# ESP8266.net
KiCad netlist of a schematic drawn in Altium Designer
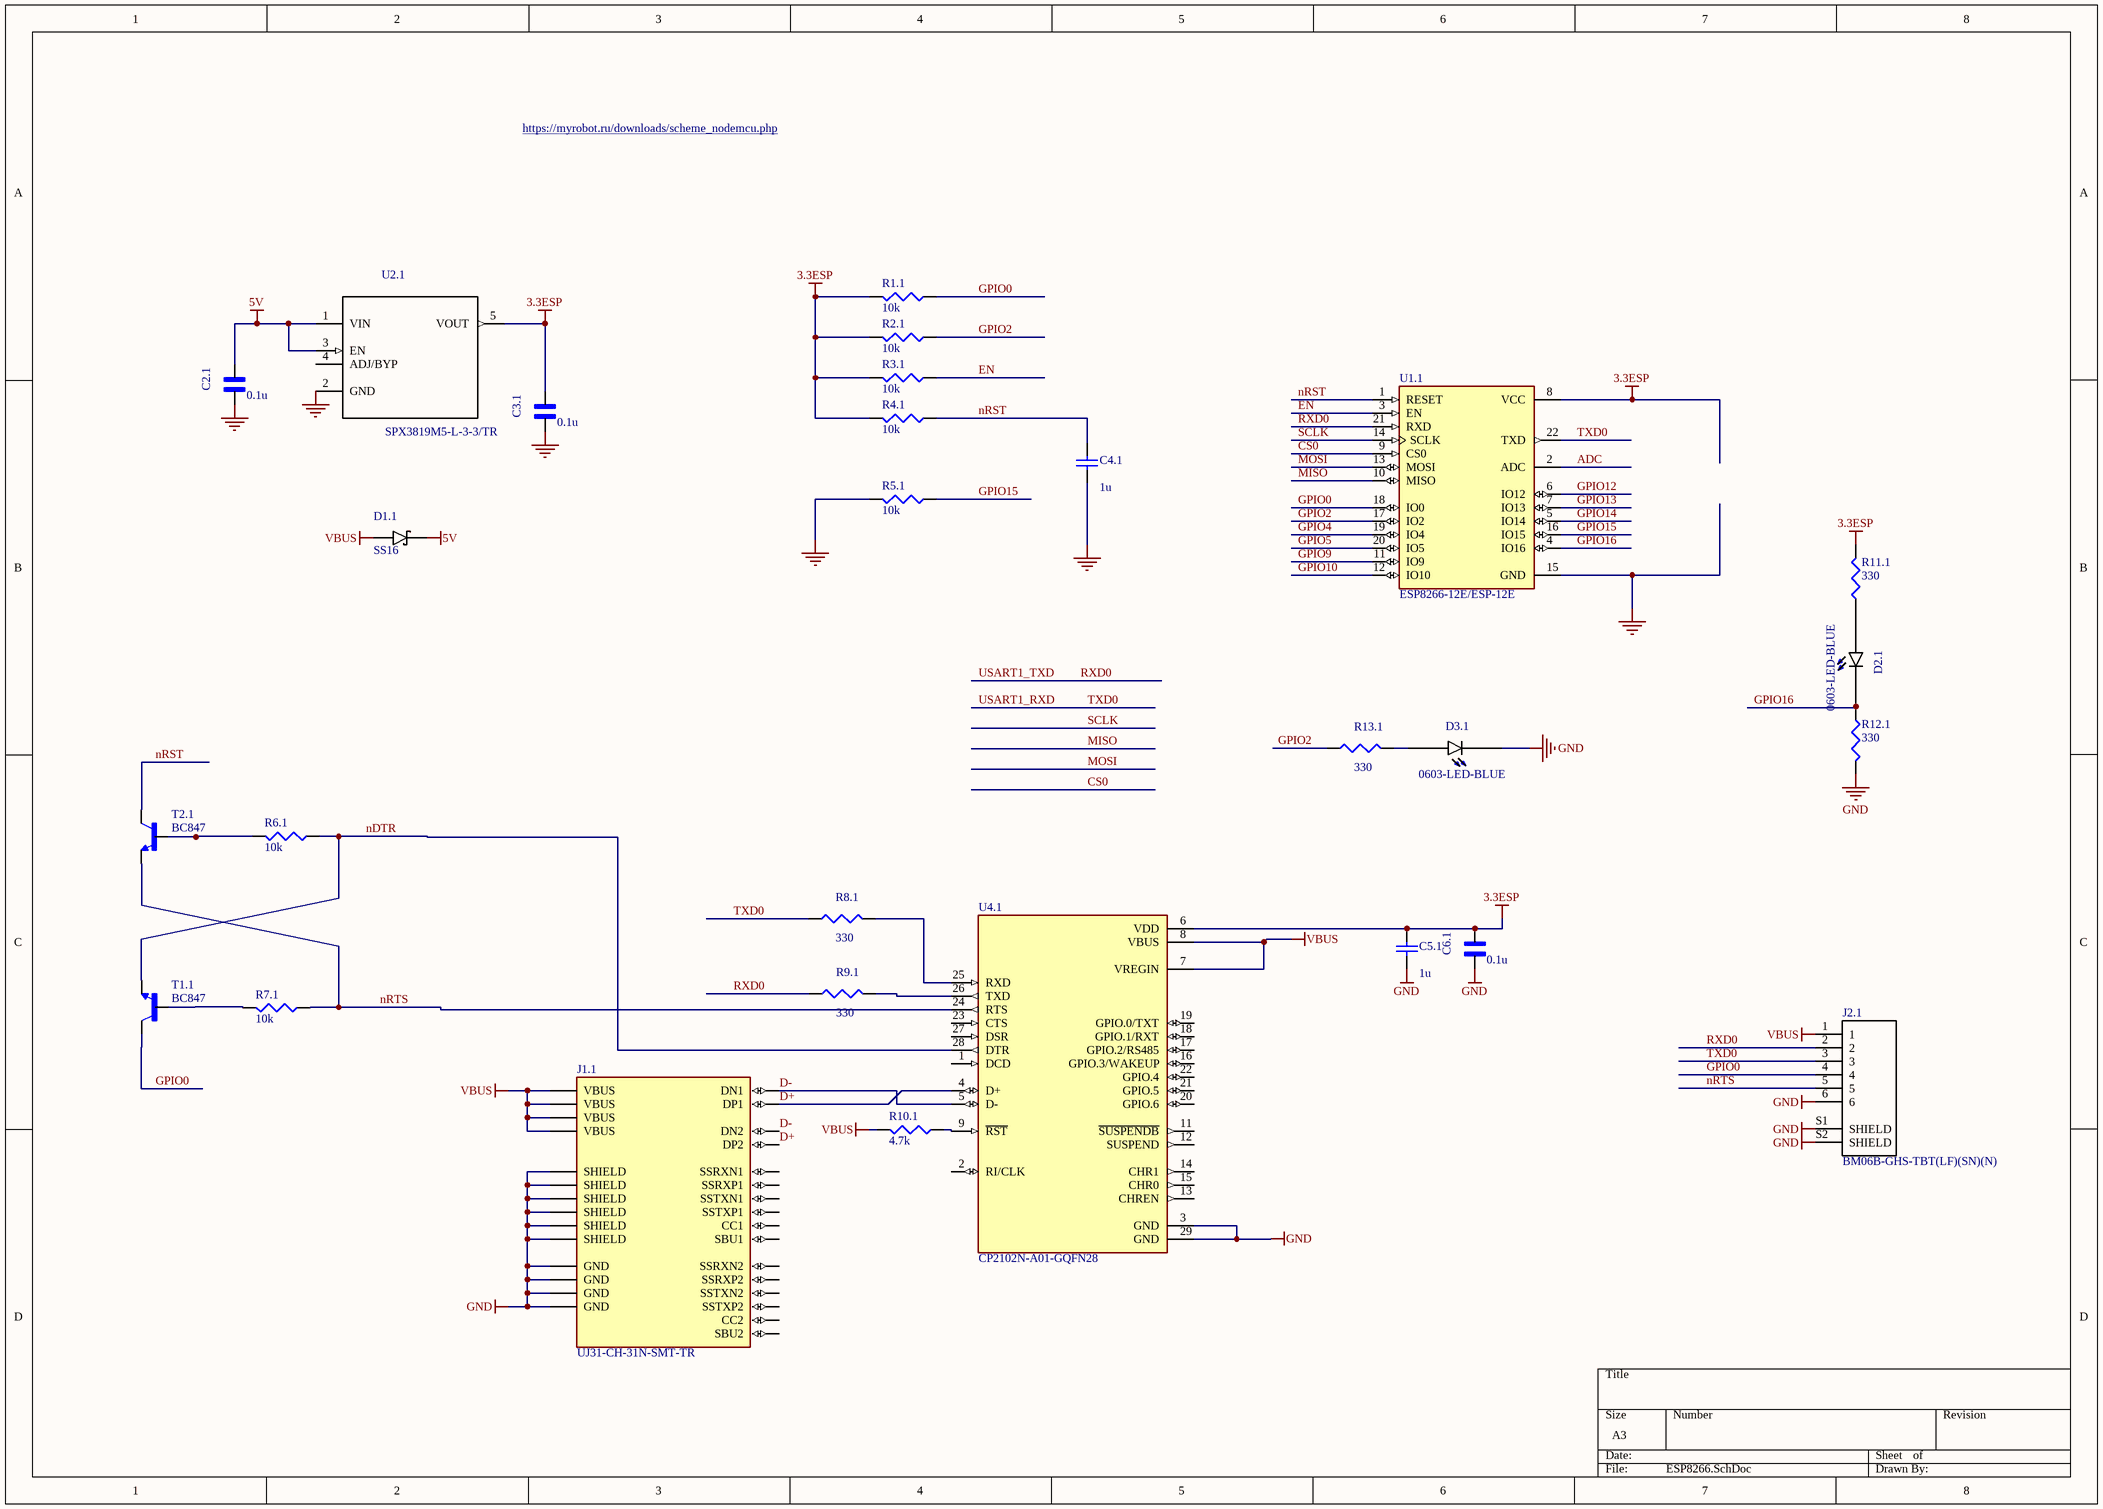
[diagram p0: ESP8266.SchDoc]

(export (version "E")
  (design (tool "Eeschema 10.0.6"))
  (components
    (comp (ref "C2.1")
      (value "0.1u")
      (footprint "*CAPC1608X90")
      (description "Cap Thin Film 0.1uf 50v 0603")
      (fields (field (name "MF") "AVX") (field (name "MP") "GX035C104MAT2-500"))
      (libsource (lib "lib") (part "GX035C104MAT2-500"))
    )
    (comp (ref "C3.1")
      (value "0.1u")
      (footprint "*CAPC1608X90")
      (description "Cap Thin Film 0.1uf 50v 0603")
      (fields (field (name "MF") "AVX") (field (name "MP") "GX035C104MAT2-500"))
      (libsource (lib "lib") (part "GX035C104MAT2-500"))
    )
    (comp (ref "C4.1")
      (value "1u")
      (footprint "1608[0603]")
      (description "Capacitor (Semiconductor SIM Model)")
      (fields (field (name "Comment") "Cap Semi") (field (name "PUBLISHER") "Altium Limited"))
      (libsource (lib "Miscellaneous Devices") (part "Cap Semi"))
    )
    (comp (ref "C5.1")
      (value "1u")
      (footprint "1608[0603]")
      (description "Capacitor (Semiconductor SIM Model)")
      (fields (field (name "Comment") "Cap Semi") (field (name "PUBLISHER") "Altium Limited"))
      (libsource (lib "Miscellaneous Devices") (part "Cap Semi"))
    )
    (comp (ref "C6.1")
      (value "0.1u")
      (footprint "*CAPC1608X90")
      (description "Cap Thin Film 0.1uf 50v 0603")
      (fields (field (name "MF") "AVX") (field (name "MP") "GX035C104MAT2-500 or CL10B104JB8NNNC"))
      (libsource (lib "lib") (part "GX035C104MAT2-500"))
    )
    (comp (ref "D1.1")
      (value "SS16")
      (footprint "*DIOM5227X250N_SS16(Primary)")
      (description "Diode Schottky 60V 1A Surface Mount SMA")
      (libsource (lib "lib") (part "SS16"))
    )
    (comp (ref "D2.1")
      (value "0603-LED-BLUE")
      (footprint "*LEDM1608X80_LTE-C1906R-14(Primary)")
      (description "LED IrLED Chip LED 2-Pin SMD T/R")
      (libsource (lib "lib") (part "LTE-C1906R-14"))
    )
    (comp (ref "D3.1")
      (value "0603-LED-BLUE")
      (footprint "*LEDM1608X80_LTE-C1906R-14(Primary)")
      (description "LED IrLED Chip LED 2-Pin SMD T/R")
      (libsource (lib "lib") (part "LTE-C1906R-14"))
    )
    (comp (ref "J1.1")
      (value "UJ31-CH-31N-SMT-TR")
      (footprint "CUI_UJ31-CH-31N-SMT-TR")
      (description "Type C, USB 3.1 Gen 2, 5 A, Right Angle, Surface Mount _SMT_, USB Receptacle")
      (fields (field (name "MF") "CUI Devices"))
      (libsource (lib "lib") (part "UJ31-CH-31N-SMT-TR"))
    )
    (comp (ref "J2.1")
      (value "BM06B-GHS-TBT(LF)(SN)(N)")
      (footprint "*JST_BM06B-GHS-TBT(LF)(SN)(N)_BM06B-GHS-TBT(LF)(SN)(N)(Primary)")
      (description "Conn Header Gh Top 6pos 1.25mm")
      (fields (field (name "MP") "BM06B-GHS-TBT_LF__SN__N_") (field (name "MF") "JST Sales"))
      (libsource (lib "lib") (part "BM06B-GHS-TBT(LF)(SN)(N)"))
    )
    (comp (ref "R1.1")
      (value "10k")
      (footprint "J1-0603")
      (description "Resistor")
      (fields (field (name "MP") "10K 1% 0603") (field (name "Comment") "Res3"))
      (libsource (lib "Miscellaneous Devices") (part "Res3"))
    )
    (comp (ref "R2.1")
      (value "10k")
      (footprint "J1-0603")
      (description "Resistor")
      (fields (field (name "MP") "10K 1% 0603") (field (name "Comment") "Res3"))
      (libsource (lib "Miscellaneous Devices") (part "Res3"))
    )
    (comp (ref "R3.1")
      (value "10k")
      (footprint "J1-0603")
      (description "Resistor")
      (fields (field (name "MP") "10K 1% 0603") (field (name "Comment") "Res3"))
      (libsource (lib "Miscellaneous Devices") (part "Res3"))
    )
    (comp (ref "R4.1")
      (value "10k")
      (footprint "J1-0603")
      (description "Resistor")
      (fields (field (name "MP") "10K 1% 0603") (field (name "Comment") "Res3"))
      (libsource (lib "Miscellaneous Devices") (part "Res3"))
    )
    (comp (ref "R5.1")
      (value "10k")
      (footprint "J1-0603")
      (description "Resistor")
      (fields (field (name "MP") "10K 1% 0603") (field (name "Comment") "Res3"))
      (libsource (lib "Miscellaneous Devices") (part "Res3"))
    )
    (comp (ref "R6.1")
      (value "10k")
      (footprint "J1-0603")
      (description "Resistor")
      (fields (field (name "MP") "10K 1% 0603") (field (name "Comment") "Res3"))
      (libsource (lib "Miscellaneous Devices") (part "Res3"))
    )
    (comp (ref "R7.1")
      (value "10k")
      (footprint "J1-0603")
      (description "Resistor")
      (fields (field (name "MP") "10K 1% 0603") (field (name "Comment") "Res3"))
      (libsource (lib "Miscellaneous Devices") (part "Res3"))
    )
    (comp (ref "R8.1")
      (value "330")
      (footprint "J1-0603")
      (description "Resistor")
      (fields (field (name "MP") "RC0603FR-07330RL") (field (name "Comment") "Res3"))
      (libsource (lib "Miscellaneous Devices") (part "Res3"))
    )
    (comp (ref "R9.1")
      (value "330")
      (footprint "J1-0603")
      (description "Resistor")
      (fields (field (name "MP") "RC0603FR-07330RL") (field (name "Comment") "Res3"))
      (libsource (lib "Miscellaneous Devices") (part "Res3"))
    )
    (comp (ref "R10.1")
      (value "4.7k")
      (footprint "J1-0603")
      (description "Resistor")
      (fields (field (name "MP") "4.7K 1% 0603") (field (name "Comment") "Res3"))
      (libsource (lib "Miscellaneous Devices") (part "Res3"))
    )
    (comp (ref "R11.1")
      (value "330")
      (footprint "J1-0603")
      (description "Resistor")
      (fields (field (name "MP") "RC0603FR-07330RL") (field (name "Comment") "Res3"))
      (libsource (lib "Miscellaneous Devices") (part "Res3"))
    )
    (comp (ref "R12.1")
      (value "330")
      (footprint "J1-0603")
      (description "Resistor")
      (fields (field (name "MP") "RC0603FR-07330RL") (field (name "Comment") "Res3"))
      (libsource (lib "Miscellaneous Devices") (part "Res3"))
    )
    (comp (ref "R13.1")
      (value "330")
      (footprint "J1-0603")
      (description "Resistor")
      (fields (field (name "MP") "RC0603FR-07330RL") (field (name "Comment") "Res3"))
      (libsource (lib "Miscellaneous Devices") (part "Res3"))
    )
    (comp (ref "T1.1")
      (value "BC847")
      (footprint "SOT23")
      (description "<b>NPN TRANSISTOR</b>")
      (fields (field (name "MF") "{'manufacturer': u'Rectron'}"))
      (libsource (lib "SnapEDA_Library") (part "BC847"))
    )
    (comp (ref "T2.1")
      (value "BC847")
      (footprint "SOT23")
      (description "<b>NPN TRANSISTOR</b>")
      (fields (field (name "MF") "{'manufacturer': u'Rectron'}"))
      (libsource (lib "") (part "BC847_1"))
    )
    (comp (ref "U1.1")
      (value "ESP8266-12E/ESP-12E")
      (footprint "XCVR_ESP8266-12E/ESP-12E")
      (description "ESP-12E WiFi Module")
      (fields (field (name "MF") "{'manufacturer': u'AI-Thinker'}"))
      (libsource (lib "SnapEDA_Library") (part "ESP8266-12E/ESP-12E"))
    )
    (comp (ref "U2.1")
      (value "SPX3819M5-L-3-3/TR")
      (footprint "*SOT95P280X145-5N")
      (description "Low Dropout Voltage Regulator, Adjustable 0.5A, В±1%, 2.5 to 16 Vin, 5-Pin SOT-23")
      (fields (field (name "MF") "MaxLinear, Inc."))
      (libsource (lib "DC_DC") (part "SPX3819M5-L"))
    )
    (comp (ref "U4.1")
      (value "CP2102N-A01-GQFN28")
      (footprint "QFN50P500X500X80-29N")
      (description "Ic Bridge Usb To Uart 28qfn")
      (fields (field (name "MF") "{'manufacturer': u'Silicon Labs'}"))
      (libsource (lib "SnapEDA_Library") (part "CP2102N-A01-GQFN28"))
    )
  )
  (nets
    (net (code "1") (name "/ADC") (class "Default")
      (node (ref "U1.1") (pin "2") (pinfunction "ADC_2") (pintype "passive"))
    )
    (net (code "2") (name "/CS0") (class "Default")
      (node (ref "U1.1") (pin "9") (pinfunction "CS0_9") (pintype "input"))
    )
    (net (code "3") (name "/D+") (class "Default")
      (node (ref "J1.1") (pin "A6") (pinfunction "DP1_A6") (pintype "bidirectional"))
      (node (ref "J1.1") (pin "B6") (pinfunction "DP2_B6") (pintype "bidirectional"))
      (node (ref "U4.1") (pin "4") (pinfunction "D+_4") (pintype "bidirectional"))
    )
    (net (code "4") (name "/D-") (class "Default")
      (node (ref "J1.1") (pin "A7") (pinfunction "DN1_A7") (pintype "bidirectional"))
      (node (ref "J1.1") (pin "B7") (pinfunction "DN2_B7") (pintype "bidirectional"))
      (node (ref "U4.1") (pin "5") (pinfunction "D-_5") (pintype "bidirectional"))
    )
    (net (code "5") (name "/EN") (class "Default")
      (node (ref "R3.1") (pin "1") (pinfunction "1_1") (pintype "passive"))
      (node (ref "U1.1") (pin "3") (pinfunction "EN_3") (pintype "input"))
    )
    (net (code "6") (name "/GPIO0") (class "Default")
      (node (ref "J2.1") (pin "4") (pinfunction "4_4") (pintype "passive"))
      (node (ref "R1.1") (pin "1") (pinfunction "1_1") (pintype "passive"))
      (node (ref "T1.1") (pin "3") (pinfunction "C_3") (pintype "passive"))
      (node (ref "U1.1") (pin "18") (pinfunction "IO0_18") (pintype "bidirectional"))
    )
    (net (code "7") (name "/GPIO2") (class "Default")
      (node (ref "R13.1") (pin "1") (pinfunction "1_1") (pintype "passive"))
      (node (ref "R2.1") (pin "1") (pinfunction "1_1") (pintype "passive"))
      (node (ref "U1.1") (pin "17") (pinfunction "IO2_17") (pintype "bidirectional"))
    )
    (net (code "8") (name "/GPIO4") (class "Default")
      (node (ref "U1.1") (pin "19") (pinfunction "IO4_19") (pintype "bidirectional"))
    )
    (net (code "9") (name "/GPIO5") (class "Default")
      (node (ref "U1.1") (pin "20") (pinfunction "IO5_20") (pintype "bidirectional"))
    )
    (net (code "10") (name "/GPIO9") (class "Default")
      (node (ref "U1.1") (pin "11") (pinfunction "IO9_11") (pintype "bidirectional"))
    )
    (net (code "11") (name "/GPIO10") (class "Default")
      (node (ref "U1.1") (pin "12") (pinfunction "IO10_12") (pintype "bidirectional"))
    )
    (net (code "12") (name "/GPIO12") (class "Default")
      (node (ref "U1.1") (pin "6") (pinfunction "IO12_6") (pintype "bidirectional"))
    )
    (net (code "13") (name "/GPIO13") (class "Default")
      (node (ref "U1.1") (pin "7") (pinfunction "IO13_7") (pintype "bidirectional"))
    )
    (net (code "14") (name "/GPIO14") (class "Default")
      (node (ref "U1.1") (pin "5") (pinfunction "IO14_5") (pintype "bidirectional"))
    )
    (net (code "15") (name "/GPIO15") (class "Default")
      (node (ref "R5.1") (pin "1") (pinfunction "1_1") (pintype "passive"))
      (node (ref "U1.1") (pin "16") (pinfunction "IO15_16") (pintype "bidirectional"))
    )
    (net (code "16") (name "/GPIO16") (class "Default")
      (node (ref "D2.1") (pin "C") (pinfunction "C_C") (pintype "passive"))
      (node (ref "R12.1") (pin "1") (pinfunction "1_1") (pintype "passive"))
      (node (ref "U1.1") (pin "4") (pinfunction "IO16_4") (pintype "bidirectional"))
    )
    (net (code "17") (name "/MISO") (class "Default")
      (node (ref "U1.1") (pin "10") (pinfunction "MISO_10") (pintype "bidirectional"))
    )
    (net (code "18") (name "/MOSI") (class "Default")
      (node (ref "U1.1") (pin "13") (pinfunction "MOSI_13") (pintype "bidirectional"))
    )
    (net (code "19") (name "/RXD0") (class "Default")
      (node (ref "J2.1") (pin "2") (pinfunction "2_2") (pintype "passive"))
      (node (ref "R9.1") (pin "1") (pinfunction "1_1") (pintype "passive"))
      (node (ref "U1.1") (pin "21") (pinfunction "RXD_21") (pintype "input"))
    )
    (net (code "20") (name "/SCLK") (class "Default")
      (node (ref "U1.1") (pin "14") (pinfunction "SCLK_14") (pintype "input"))
    )
    (net (code "21") (name "/TXD0") (class "Default")
      (node (ref "J2.1") (pin "3") (pinfunction "3_3") (pintype "passive"))
      (node (ref "R8.1") (pin "1") (pinfunction "1_1") (pintype "passive"))
      (node (ref "U1.1") (pin "22") (pinfunction "TXD_22") (pintype "output"))
    )
    (net (code "22") (name "/nDTR") (class "Default")
      (node (ref "R6.1") (pin "1") (pinfunction "1_1") (pintype "passive"))
      (node (ref "T1.1") (pin "2") (pinfunction "E_2") (pintype "passive"))
      (node (ref "U4.1") (pin "28") (pinfunction "DTR_28") (pintype "output"))
    )
    (net (code "23") (name "/nRST") (class "Default")
      (node (ref "C4.1") (pin "1") (pinfunction "1_1") (pintype "passive"))
      (node (ref "R4.1") (pin "1") (pinfunction "1_1") (pintype "passive"))
      (node (ref "T2.1") (pin "3") (pinfunction "C_3") (pintype "passive"))
      (node (ref "U1.1") (pin "1") (pinfunction "RESET_1") (pintype "input"))
    )
    (net (code "24") (name "/nRTS") (class "Default")
      (node (ref "J2.1") (pin "5") (pinfunction "5_5") (pintype "passive"))
      (node (ref "R7.1") (pin "1") (pinfunction "1_1") (pintype "passive"))
      (node (ref "T2.1") (pin "2") (pinfunction "E_2") (pintype "passive"))
      (node (ref "U4.1") (pin "24") (pinfunction "RTS_24") (pintype "output"))
    )
    (net (code "25") (name "3.3ESP") (class "Default")
      (node (ref "C3.1") (pin "1") (pinfunction "1_1") (pintype "passive"))
      (node (ref "C5.1") (pin "1") (pinfunction "1_1") (pintype "passive"))
      (node (ref "C6.1") (pin "1") (pinfunction "1_1") (pintype "passive"))
      (node (ref "R1.1") (pin "2") (pinfunction "2_2") (pintype "passive"))
      (node (ref "R11.1") (pin "2") (pinfunction "2_2") (pintype "passive"))
      (node (ref "R2.1") (pin "2") (pinfunction "2_2") (pintype "passive"))
      (node (ref "R3.1") (pin "2") (pinfunction "2_2") (pintype "passive"))
      (node (ref "R4.1") (pin "2") (pinfunction "2_2") (pintype "passive"))
      (node (ref "U1.1") (pin "8") (pinfunction "VCC_8") (pintype "power_in"))
      (node (ref "U2.1") (pin "5") (pinfunction "VOUT_5") (pintype "output"))
      (node (ref "U4.1") (pin "6") (pinfunction "VDD_6") (pintype "power_in"))
    )
    (net (code "26") (name "5V") (class "Default")
      (node (ref "C2.1") (pin "1") (pinfunction "1_1") (pintype "passive"))
      (node (ref "D1.1") (pin "C") (pinfunction "K_C") (pintype "passive"))
      (node (ref "U2.1") (pin "1") (pinfunction "VIN_1") (pintype "power_in"))
      (node (ref "U2.1") (pin "3") (pinfunction "EN_3") (pintype "input"))
    )
    (net (code "27") (name "GND") (class "Default")
      (node (ref "C2.1") (pin "2") (pinfunction "2_2") (pintype "passive"))
      (node (ref "C3.1") (pin "2") (pinfunction "2_2") (pintype "passive"))
      (node (ref "C4.1") (pin "2") (pinfunction "2_2") (pintype "passive"))
      (node (ref "C5.1") (pin "2") (pinfunction "2_2") (pintype "passive"))
      (node (ref "C6.1") (pin "2") (pinfunction "2_2") (pintype "passive"))
      (node (ref "D3.1") (pin "C") (pinfunction "C_C") (pintype "passive"))
      (node (ref "J1.1") (pin "A1") (pinfunction "GND_A1") (pintype "power_in"))
      (node (ref "J1.1") (pin "A12") (pinfunction "GND_A12") (pintype "power_in"))
      (node (ref "J1.1") (pin "B1") (pinfunction "GND_B1") (pintype "power_in"))
      (node (ref "J1.1") (pin "B12") (pinfunction "GND_B12") (pintype "power_in"))
      (node (ref "J1.1") (pin "SH1") (pinfunction "SHIELD_SH1") (pintype "power_in"))
      (node (ref "J1.1") (pin "SH2") (pinfunction "SHIELD_SH2") (pintype "power_in"))
      (node (ref "J1.1") (pin "SH3") (pinfunction "SHIELD_SH3") (pintype "power_in"))
      (node (ref "J1.1") (pin "SH4") (pinfunction "SHIELD_SH4") (pintype "power_in"))
      (node (ref "J1.1") (pin "SH5") (pinfunction "SHIELD_SH5") (pintype "power_in"))
      (node (ref "J1.1") (pin "SH6") (pinfunction "SHIELD_SH6") (pintype "power_in"))
      (node (ref "J2.1") (pin "6") (pinfunction "6_6") (pintype "passive"))
      (node (ref "J2.1") (pin "S1") (pinfunction "SHIELD_S1") (pintype "passive"))
      (node (ref "J2.1") (pin "S2") (pinfunction "SHIELD_S2") (pintype "passive"))
      (node (ref "R12.1") (pin "2") (pinfunction "2_2") (pintype "passive"))
      (node (ref "R5.1") (pin "2") (pinfunction "2_2") (pintype "passive"))
      (node (ref "U1.1") (pin "15") (pinfunction "GND_15") (pintype "power_in"))
      (node (ref "U2.1") (pin "2") (pinfunction "GND_2") (pintype "passive"))
      (node (ref "U4.1") (pin "29") (pinfunction "GND_29") (pintype "power_in"))
      (node (ref "U4.1") (pin "3") (pinfunction "GND_3") (pintype "power_in"))
    )
    (net (code "28") (name "Net-(D2.1-PadA)") (class "Default")
      (node (ref "D2.1") (pin "A") (pinfunction "A_A") (pintype "passive"))
      (node (ref "R11.1") (pin "1") (pinfunction "1_1") (pintype "passive"))
    )
    (net (code "29") (name "Net-(D3.1-PadA)") (class "Default")
      (node (ref "D3.1") (pin "A") (pinfunction "A_A") (pintype "passive"))
      (node (ref "R13.1") (pin "2") (pinfunction "2_2") (pintype "passive"))
    )
    (net (code "30") (name "Net-(T1.1-B)") (class "Default")
      (node (ref "R7.1") (pin "2") (pinfunction "2_2") (pintype "passive"))
      (node (ref "T1.1") (pin "1") (pinfunction "B_1") (pintype "passive"))
    )
    (net (code "31") (name "Net-(T2.1-B)") (class "Default")
      (node (ref "R6.1") (pin "2") (pinfunction "2_2") (pintype "passive"))
      (node (ref "T2.1") (pin "1") (pinfunction "B_1") (pintype "passive"))
    )
    (net (code "32") (name "Net-(U4.1-RXD)") (class "Default")
      (node (ref "R8.1") (pin "2") (pinfunction "2_2") (pintype "passive"))
      (node (ref "U4.1") (pin "25") (pinfunction "RXD_25") (pintype "input"))
    )
    (net (code "33") (name "Net-(U4.1-TXD)") (class "Default")
      (node (ref "R9.1") (pin "2") (pinfunction "2_2") (pintype "passive"))
      (node (ref "U4.1") (pin "26") (pinfunction "TXD_26") (pintype "output"))
    )
    (net (code "34") (name "Net-(U4.1-~{RST})") (class "Default")
      (node (ref "R10.1") (pin "1") (pinfunction "1_1") (pintype "passive"))
      (node (ref "U4.1") (pin "9") (pinfunction "~{RST}_9") (pintype "input"))
    )
    (net (code "35") (name "VBUS") (class "Default")
      (node (ref "D1.1") (pin "A") (pinfunction "A_A") (pintype "passive"))
      (node (ref "J1.1") (pin "A4") (pinfunction "VBUS_A4") (pintype "power_in"))
      (node (ref "J1.1") (pin "A9") (pinfunction "VBUS_A9") (pintype "power_in"))
      (node (ref "J1.1") (pin "B4") (pinfunction "VBUS_B4") (pintype "power_in"))
      (node (ref "J1.1") (pin "B9") (pinfunction "VBUS_B9") (pintype "power_in"))
      (node (ref "J2.1") (pin "1") (pinfunction "1_1") (pintype "passive"))
      (node (ref "R10.1") (pin "2") (pinfunction "2_2") (pintype "passive"))
      (node (ref "U4.1") (pin "7") (pinfunction "VREGIN_7") (pintype "power_in"))
      (node (ref "U4.1") (pin "8") (pinfunction "VBUS_8") (pintype "power_in"))
    )
    (net (code "36") (name "unconnected-(J1.1-CC1-PadA5)") (class "Default")
      (node (ref "J1.1") (pin "A5") (pinfunction "CC1_A5") (pintype "bidirectional"))
    )
    (net (code "37") (name "unconnected-(J1.1-CC2-PadB5)") (class "Default")
      (node (ref "J1.1") (pin "B5") (pinfunction "CC2_B5") (pintype "bidirectional"))
    )
    (net (code "38") (name "unconnected-(J1.1-SBU1-PadA8)") (class "Default")
      (node (ref "J1.1") (pin "A8") (pinfunction "SBU1_A8") (pintype "bidirectional"))
    )
    (net (code "39") (name "unconnected-(J1.1-SBU2-PadB8)") (class "Default")
      (node (ref "J1.1") (pin "B8") (pinfunction "SBU2_B8") (pintype "bidirectional"))
    )
    (net (code "40") (name "unconnected-(J1.1-SSRXN1-PadB10)") (class "Default")
      (node (ref "J1.1") (pin "B10") (pinfunction "SSRXN1_B10") (pintype "bidirectional"))
    )
    (net (code "41") (name "unconnected-(J1.1-SSRXN2-PadA10)") (class "Default")
      (node (ref "J1.1") (pin "A10") (pinfunction "SSRXN2_A10") (pintype "bidirectional"))
    )
    (net (code "42") (name "unconnected-(J1.1-SSRXP1-PadB11)") (class "Default")
      (node (ref "J1.1") (pin "B11") (pinfunction "SSRXP1_B11") (pintype "bidirectional"))
    )
    (net (code "43") (name "unconnected-(J1.1-SSRXP2-PadA11)") (class "Default")
      (node (ref "J1.1") (pin "A11") (pinfunction "SSRXP2_A11") (pintype "bidirectional"))
    )
    (net (code "44") (name "unconnected-(J1.1-SSTXN1-PadA3)") (class "Default")
      (node (ref "J1.1") (pin "A3") (pinfunction "SSTXN1_A3") (pintype "bidirectional"))
    )
    (net (code "45") (name "unconnected-(J1.1-SSTXN2-PadB3)") (class "Default")
      (node (ref "J1.1") (pin "B3") (pinfunction "SSTXN2_B3") (pintype "bidirectional"))
    )
    (net (code "46") (name "unconnected-(J1.1-SSTXP1-PadA2)") (class "Default")
      (node (ref "J1.1") (pin "A2") (pinfunction "SSTXP1_A2") (pintype "bidirectional"))
    )
    (net (code "47") (name "unconnected-(J1.1-SSTXP2-PadB2)") (class "Default")
      (node (ref "J1.1") (pin "B2") (pinfunction "SSTXP2_B2") (pintype "bidirectional"))
    )
    (net (code "48") (name "unconnected-(U2.1-ADJ{slash}BYP-Pad4)") (class "Default")
      (node (ref "U2.1") (pin "4") (pinfunction "ADJ/BYP_4") (pintype "passive"))
    )
    (net (code "49") (name "unconnected-(U4.1-CHR0-Pad15)") (class "Default")
      (node (ref "U4.1") (pin "15") (pinfunction "CHR0_15") (pintype "output"))
    )
    (net (code "50") (name "unconnected-(U4.1-CHR1-Pad14)") (class "Default")
      (node (ref "U4.1") (pin "14") (pinfunction "CHR1_14") (pintype "output"))
    )
    (net (code "51") (name "unconnected-(U4.1-CHREN-Pad13)") (class "Default")
      (node (ref "U4.1") (pin "13") (pinfunction "CHREN_13") (pintype "output"))
    )
    (net (code "52") (name "unconnected-(U4.1-CTS-Pad23)") (class "Default")
      (node (ref "U4.1") (pin "23") (pinfunction "CTS_23") (pintype "input"))
    )
    (net (code "53") (name "unconnected-(U4.1-DCD-Pad1)") (class "Default")
      (node (ref "U4.1") (pin "1") (pinfunction "DCD_1") (pintype "input"))
    )
    (net (code "54") (name "unconnected-(U4.1-DSR-Pad27)") (class "Default")
      (node (ref "U4.1") (pin "27") (pinfunction "DSR_27") (pintype "input"))
    )
    (net (code "55") (name "unconnected-(U4.1-GPIO.0{slash}TXT-Pad19)") (class "Default")
      (node (ref "U4.1") (pin "19") (pinfunction "GPIO.0/TXT_19") (pintype "bidirectional"))
    )
    (net (code "56") (name "unconnected-(U4.1-GPIO.1{slash}RXT-Pad18)") (class "Default")
      (node (ref "U4.1") (pin "18") (pinfunction "GPIO.1/RXT_18") (pintype "bidirectional"))
    )
    (net (code "57") (name "unconnected-(U4.1-GPIO.2{slash}RS485-Pad17)") (class "Default")
      (node (ref "U4.1") (pin "17") (pinfunction "GPIO.2/RS485_17") (pintype "bidirectional"))
    )
    (net (code "58") (name "unconnected-(U4.1-GPIO.3{slash}WAKEUP-Pad16)") (class "Default")
      (node (ref "U4.1") (pin "16") (pinfunction "GPIO.3/WAKEUP_16") (pintype "bidirectional"))
    )
    (net (code "59") (name "unconnected-(U4.1-GPIO.4-Pad22)") (class "Default")
      (node (ref "U4.1") (pin "22") (pinfunction "GPIO.4_22") (pintype "bidirectional"))
    )
    (net (code "60") (name "unconnected-(U4.1-GPIO.5-Pad21)") (class "Default")
      (node (ref "U4.1") (pin "21") (pinfunction "GPIO.5_21") (pintype "bidirectional"))
    )
    (net (code "61") (name "unconnected-(U4.1-GPIO.6-Pad20)") (class "Default")
      (node (ref "U4.1") (pin "20") (pinfunction "GPIO.6_20") (pintype "bidirectional"))
    )
    (net (code "62") (name "unconnected-(U4.1-RI{slash}CLK-Pad2)") (class "Default")
      (node (ref "U4.1") (pin "2") (pinfunction "RI/CLK_2") (pintype "bidirectional"))
    )
    (net (code "63") (name "unconnected-(U4.1-SUSPEND-Pad12)") (class "Default")
      (node (ref "U4.1") (pin "12") (pinfunction "SUSPEND_12") (pintype "output"))
    )
    (net (code "64") (name "unconnected-(U4.1-~{SUSPENDB}-Pad11)") (class "Default")
      (node (ref "U4.1") (pin "11") (pinfunction "~{SUSPENDB}_11") (pintype "output"))
    )
  )
)
